# BBTC-PSU.net
KiCad netlist of a schematic drawn in Altium Designer
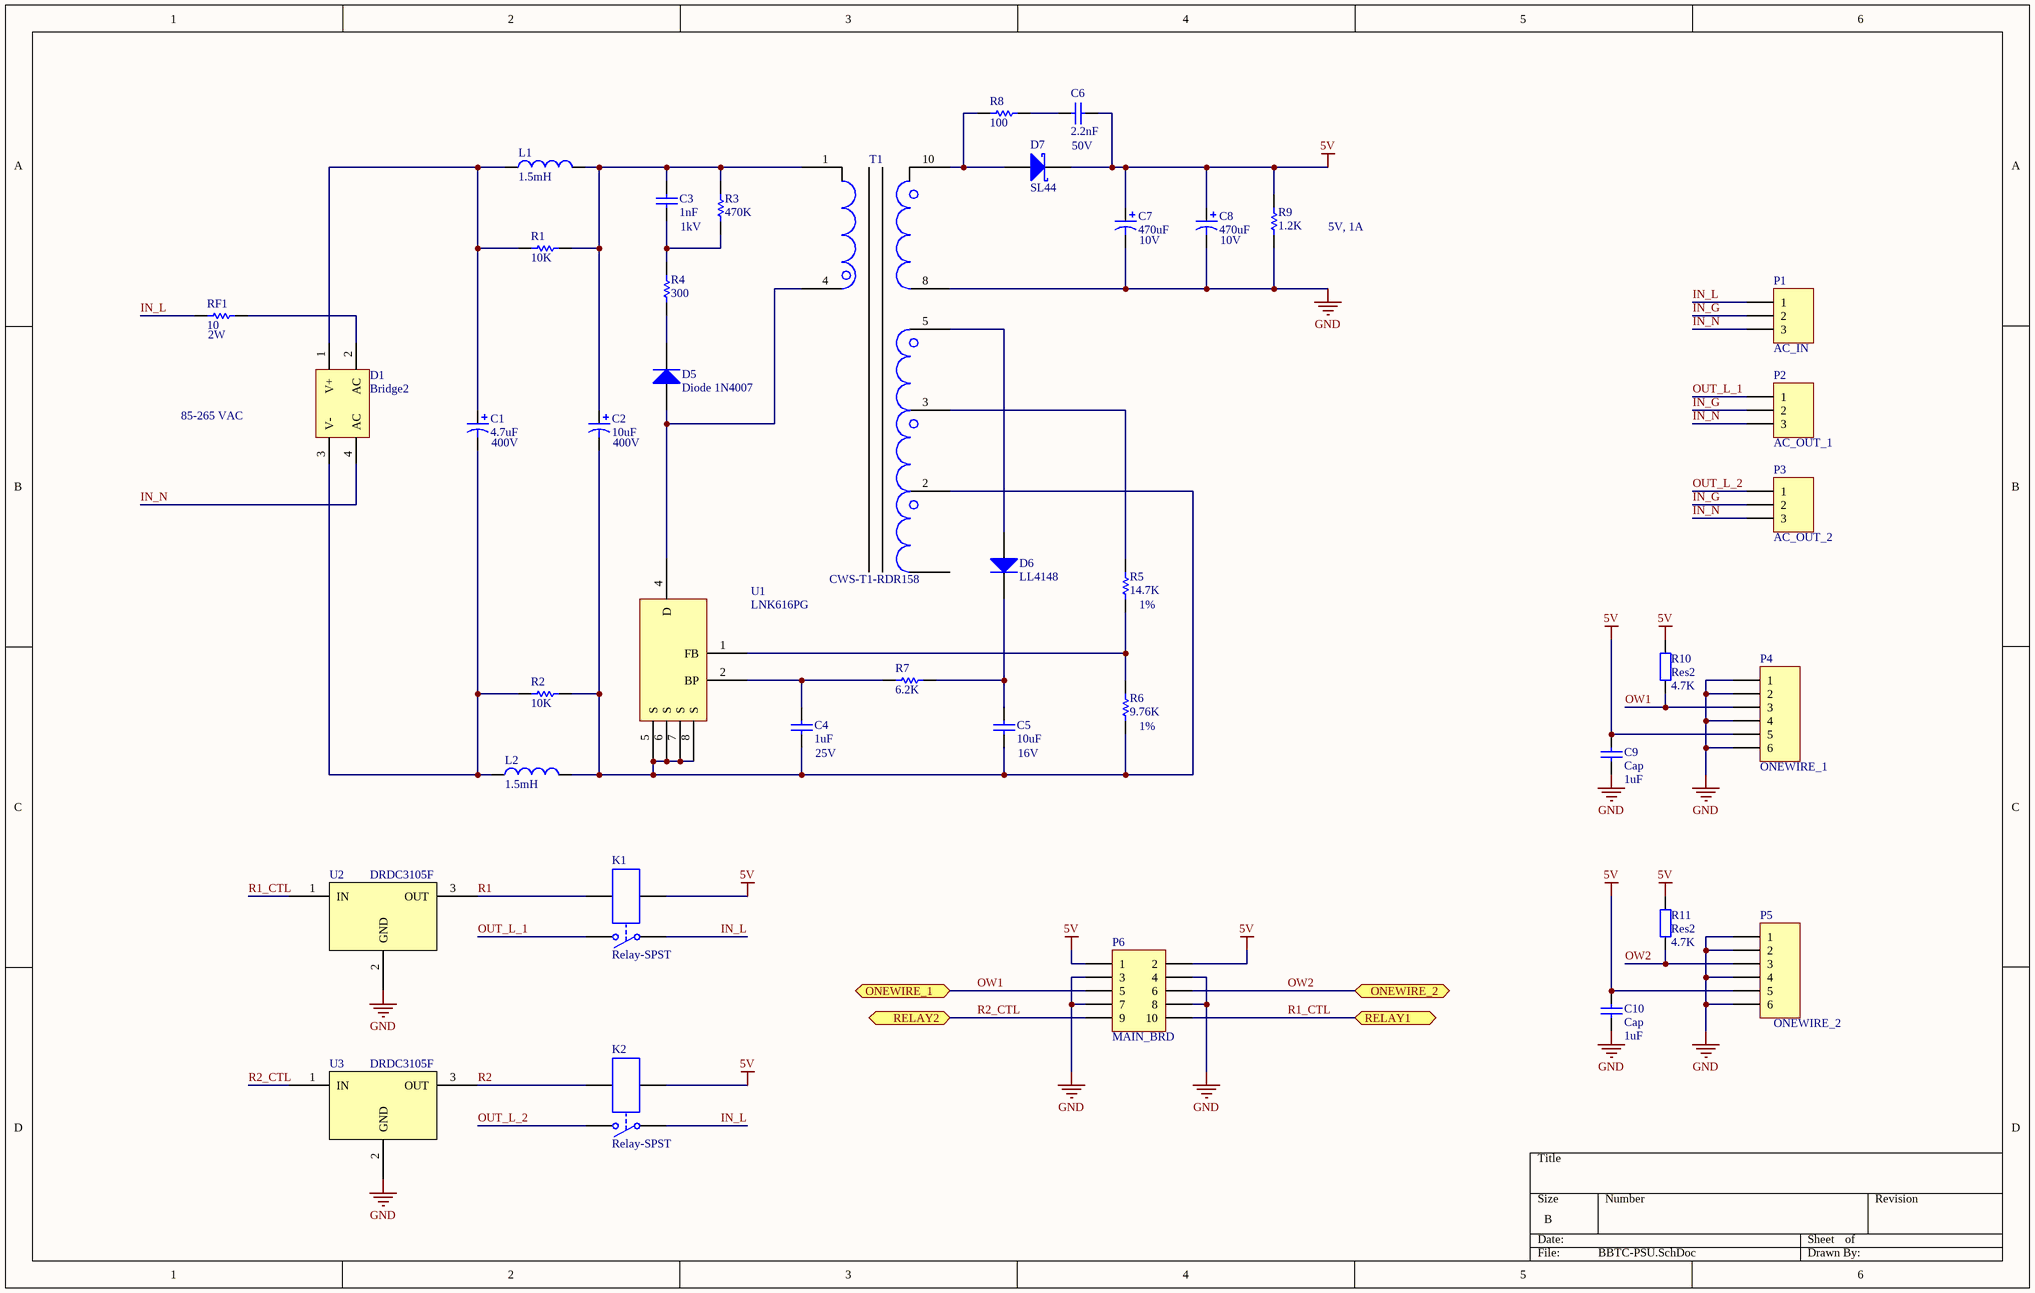
[diagram p0: BBTC-PSU.SchDoc]

(export (version "E")
  (design (tool "Eeschema 10.0.6"))
  (components
    (comp (ref "C1")
      (value "4.7uF")
      (footprint "CAP-10D-5L")
      (description "Polarized Capacitor (Radial)")
      (fields (field (name "VOLTAGE") "400V"))
      (libsource (lib "Miscellaneous Devices") (part "Cap Pol1"))
    )
    (comp (ref "C2")
      (value "10uF")
      (footprint "CAP-12.5D-5L")
      (description "Polarized Capacitor (Radial)")
      (fields (field (name "VOLTAGE") "400V"))
      (libsource (lib "Miscellaneous Devices") (part "Cap Pol1"))
    )
    (comp (ref "C3")
      (value "1nF")
      (footprint "0805")
      (description "Capacitor")
      (fields (field (name "VOLTAGE") "1kV"))
      (libsource (lib "Miscellaneous Devices") (part "Cap"))
    )
    (comp (ref "C4")
      (value "1uF")
      (footprint "0805")
      (description "Capacitor")
      (fields (field (name "VOLTAGE") "25V"))
      (libsource (lib "Miscellaneous Devices") (part "Cap"))
    )
    (comp (ref "C5")
      (value "10uF")
      (footprint "0805")
      (description "Capacitor")
      (fields (field (name "VOLTAGE") "16V"))
      (libsource (lib "Miscellaneous Devices") (part "Cap"))
    )
    (comp (ref "C6")
      (value "2.2nF")
      (footprint "0805")
      (description "Capacitor")
      (fields (field (name "VOLTAGE") "50V"))
      (libsource (lib "Miscellaneous Devices") (part "Cap"))
    )
    (comp (ref "C7")
      (value "470uF")
      (footprint "CAP-8D-3.5L")
      (description "Polarized Capacitor (Radial)")
      (fields (field (name "VOLTAGE") "10V"))
      (libsource (lib "Miscellaneous Devices") (part "Cap Pol1"))
    )
    (comp (ref "C8")
      (value "470uF")
      (footprint "CAP-8D-3.5L")
      (description "Polarized Capacitor (Radial)")
      (fields (field (name "VOLTAGE") "10V"))
      (libsource (lib "Miscellaneous Devices") (part "Cap Pol1"))
    )
    (comp (ref "C9")
      (value "Cap")
      (footprint "0603")
      (description "Capacitor")
      (fields (field (name "ALTIUM_VALUE") "1uF"))
      (libsource (lib "Miscellaneous Devices") (part "Cap"))
    )
    (comp (ref "C10")
      (value "Cap")
      (footprint "0603")
      (description "Capacitor")
      (fields (field (name "ALTIUM_VALUE") "1uF"))
      (libsource (lib "Miscellaneous Devices") (part "Cap"))
    )
    (comp (ref "D1")
      (value "Bridge2")
      (footprint "DF1510S-E3/77")
      (description "Diode Bridge")
      (libsource (lib "Miscellaneous Devices") (part "Bridge2"))
    )
    (comp (ref "D5")
      (value "Diode 1N4007")
      (footprint "Diode-Wide")
      (description "1 Amp General Purpose Rectifier")
      (libsource (lib "Miscellaneous Devices") (part "Diode 1N4007"))
    )
    (comp (ref "D6")
      (value "LL4148")
      (footprint "SOD-80")
      (description "Default Diode")
      (libsource (lib "Miscellaneous Devices") (part "Diode"))
    )
    (comp (ref "D7")
      (value "SL44")
      (footprint "DIODE_SMC")
      (description "Schottky Diode")
      (libsource (lib "Miscellaneous Devices") (part "D Schottky"))
    )
    (comp (ref "K1")
      (value "Relay-SPST")
      (footprint "PB134005")
      (description "Single-Pole Single-Throw Relay")
      (fields (field (name "PUBLISHER") "Altium Limited"))
      (libsource (lib "Miscellaneous Devices") (part "Relay-SPST"))
    )
    (comp (ref "K2")
      (value "Relay-SPST")
      (footprint "PB134005")
      (description "Single-Pole Single-Throw Relay")
      (fields (field (name "PUBLISHER") "Altium Limited"))
      (libsource (lib "Miscellaneous Devices") (part "Relay-SPST"))
    )
    (comp (ref "L1")
      (value "1.5mH")
      (footprint "TSL0808")
      (description "Inductor")
      (libsource (lib "Miscellaneous Devices") (part "Inductor"))
    )
    (comp (ref "L2")
      (value "1.5mH")
      (footprint "TSL0808")
      (description "Inductor")
      (libsource (lib "Miscellaneous Devices") (part "Inductor"))
    )
    (comp (ref "P1")
      (value "AC_IN")
      (footprint "B3P-VH(LF)(SN)")
      (description "Header, 3-Pin")
      (fields (field (name "PUBLISHER") "Altium Limited"))
      (libsource (lib "Miscellaneous Connectors") (part "Header 3"))
    )
    (comp (ref "P2")
      (value "AC_OUT_1")
      (footprint "B3P-VH(LF)(SN)")
      (description "Header, 3-Pin")
      (fields (field (name "PUBLISHER") "Altium Limited"))
      (libsource (lib "Miscellaneous Connectors") (part "Header 3"))
    )
    (comp (ref "P3")
      (value "AC_OUT_2")
      (footprint "B3P-VH(LF)(SN)")
      (description "Header, 3-Pin")
      (fields (field (name "PUBLISHER") "Altium Limited"))
      (libsource (lib "Miscellaneous Connectors") (part "Header 3"))
    )
    (comp (ref "P4")
      (value "ONEWIRE_1")
      (footprint "CONN MOD JACK R/A 6P6C")
      (description "Header, 6-Pin")
      (libsource (lib "Miscellaneous Connectors") (part "Header 6"))
    )
    (comp (ref "P5")
      (value "ONEWIRE_2")
      (footprint "CONN MOD JACK R/A 6P6C")
      (description "Header, 6-Pin")
      (libsource (lib "Miscellaneous Connectors") (part "Header 6"))
    )
    (comp (ref "P6")
      (value "MAIN_BRD")
      (footprint "5X2 PIN PTH HEADER - 2MM")
      (description "Header, 5-Pin, Dual row")
      (libsource (lib "Miscellaneous Connectors") (part "Header 5X2"))
    )
    (comp (ref "R1")
      (value "10K")
      (footprint "1206")
      (description "Resistor")
      (libsource (lib "Miscellaneous Devices") (part "Res1"))
    )
    (comp (ref "R2")
      (value "10K")
      (footprint "1206")
      (description "Resistor")
      (libsource (lib "Miscellaneous Devices") (part "Res1"))
    )
    (comp (ref "R3")
      (value "470K")
      (footprint "0805")
      (description "Resistor")
      (libsource (lib "Miscellaneous Devices") (part "Res1"))
    )
    (comp (ref "R4")
      (value "300")
      (footprint "1206")
      (description "Resistor")
      (libsource (lib "Miscellaneous Devices") (part "Res1"))
    )
    (comp (ref "R5")
      (value "14.7K")
      (footprint "0603")
      (description "Resistor")
      (fields (field (name "TOLERANCE") "1%"))
      (libsource (lib "Miscellaneous Devices") (part "Res1"))
    )
    (comp (ref "R6")
      (value "9.76K")
      (footprint "0603")
      (description "Resistor")
      (fields (field (name "TOLERANCE") "1%"))
      (libsource (lib "Miscellaneous Devices") (part "Res1"))
    )
    (comp (ref "R7")
      (value "6.2K")
      (footprint "0603")
      (description "Resistor")
      (libsource (lib "Miscellaneous Devices") (part "Res1"))
    )
    (comp (ref "R8")
      (value "100")
      (footprint "0805")
      (description "Resistor")
      (libsource (lib "Miscellaneous Devices") (part "Res1"))
    )
    (comp (ref "R9")
      (value "1.2K")
      (footprint "0805")
      (description "Resistor")
      (libsource (lib "Miscellaneous Devices") (part "Res1"))
    )
    (comp (ref "R10")
      (value "Res2")
      (footprint "0603")
      (description "Resistor")
      (fields (field (name "ALTIUM_VALUE") "4.7K"))
      (libsource (lib "Miscellaneous Devices") (part "Res2"))
    )
    (comp (ref "R11")
      (value "Res2")
      (footprint "0603")
      (description "Resistor")
      (fields (field (name "ALTIUM_VALUE") "4.7K"))
      (libsource (lib "Miscellaneous Devices") (part "Res2"))
    )
    (comp (ref "RF1")
      (value "10")
      (footprint "Res Wide")
      (description "Resistor")
      (fields (field (name "POWER") "2W"))
      (libsource (lib "Miscellaneous Devices") (part "Res1"))
    )
    (comp (ref "T1")
      (value "CWS-T1-RDR158")
      (footprint "CWS-T1-RDR158")
      (description "Flyback transformer")
      (libsource (lib "BrewBit") (part "CWS-T1-RDR158"))
    )
    (comp (ref "U1")
      (value "LNK616PG")
      (footprint "LNK6XX")
      (description "Energy-Efficient, Accurate CV/CC Switcher  for Adapters and Chargers")
      (libsource (lib "BrewBit") (part "LNK616PG"))
    )
    (comp (ref "U2")
      (value "DRDC3105F")
      (footprint "SOT23")
      (description "INTEGRATED RELAY, INDUCTIVE LOAD DRIVER")
      (libsource (lib "BrewBit") (part "DRDC3105F"))
    )
    (comp (ref "U3")
      (value "DRDC3105F")
      (footprint "SOT23")
      (description "INTEGRATED RELAY, INDUCTIVE LOAD DRIVER")
      (libsource (lib "BrewBit") (part "DRDC3105F"))
    )
  )
  (nets
    (net (code "1") (name "/IN_G") (class "Default")
      (node (ref "P1") (pin "2") (pinfunction "2_2") (pintype "passive"))
      (node (ref "P2") (pin "2") (pinfunction "2_2") (pintype "passive"))
      (node (ref "P3") (pin "2") (pinfunction "2_2") (pintype "passive"))
    )
    (net (code "2") (name "/IN_L") (class "Default")
      (node (ref "K1") (pin "1") (pinfunction "1_1") (pintype "passive"))
      (node (ref "K2") (pin "1") (pinfunction "1_1") (pintype "passive"))
      (node (ref "P1") (pin "1") (pinfunction "1_1") (pintype "passive"))
      (node (ref "RF1") (pin "1") (pinfunction "1_1") (pintype "passive"))
    )
    (net (code "3") (name "/IN_N") (class "Default")
      (node (ref "D1") (pin "4") (pinfunction "AC_4") (pintype "passive"))
      (node (ref "P1") (pin "3") (pinfunction "3_3") (pintype "passive"))
      (node (ref "P2") (pin "3") (pinfunction "3_3") (pintype "passive"))
      (node (ref "P3") (pin "3") (pinfunction "3_3") (pintype "passive"))
    )
    (net (code "4") (name "/OUT_L_1") (class "Default")
      (node (ref "K1") (pin "2") (pinfunction "2_2") (pintype "passive"))
      (node (ref "P2") (pin "1") (pinfunction "1_1") (pintype "passive"))
    )
    (net (code "5") (name "/OUT_L_2") (class "Default")
      (node (ref "K2") (pin "2") (pinfunction "2_2") (pintype "passive"))
      (node (ref "P3") (pin "1") (pinfunction "1_1") (pintype "passive"))
    )
    (net (code "6") (name "/OW1") (class "Default")
      (node (ref "P4") (pin "3") (pinfunction "3_3") (pintype "passive"))
      (node (ref "P6") (pin "5") (pinfunction "5_5") (pintype "passive"))
      (node (ref "R10") (pin "1") (pinfunction "1_1") (pintype "passive"))
    )
    (net (code "7") (name "/OW2") (class "Default")
      (node (ref "P5") (pin "3") (pinfunction "3_3") (pintype "passive"))
      (node (ref "P6") (pin "6") (pinfunction "6_6") (pintype "passive"))
      (node (ref "R11") (pin "1") (pinfunction "1_1") (pintype "passive"))
    )
    (net (code "8") (name "/R1") (class "Default")
      (node (ref "K1") (pin "4") (pinfunction "4_4") (pintype "passive"))
      (node (ref "U2") (pin "3") (pinfunction "OUT_3") (pintype "passive"))
    )
    (net (code "9") (name "/R1_CTL") (class "Default")
      (node (ref "P6") (pin "10") (pinfunction "10_10") (pintype "passive"))
      (node (ref "U2") (pin "1") (pinfunction "IN_1") (pintype "passive"))
    )
    (net (code "10") (name "/R2") (class "Default")
      (node (ref "K2") (pin "4") (pinfunction "4_4") (pintype "passive"))
      (node (ref "U3") (pin "3") (pinfunction "OUT_3") (pintype "passive"))
    )
    (net (code "11") (name "/R2_CTL") (class "Default")
      (node (ref "P6") (pin "9") (pinfunction "9_9") (pintype "passive"))
      (node (ref "U3") (pin "1") (pinfunction "IN_1") (pintype "passive"))
    )
    (net (code "12") (name "5V") (class "Default")
      (node (ref "C10") (pin "2") (pinfunction "2_2") (pintype "passive"))
      (node (ref "C6") (pin "1") (pinfunction "1_1") (pintype "passive"))
      (node (ref "C7") (pin "1") (pinfunction "1_1") (pintype "passive"))
      (node (ref "C8") (pin "1") (pinfunction "1_1") (pintype "passive"))
      (node (ref "C9") (pin "2") (pinfunction "2_2") (pintype "passive"))
      (node (ref "D7") (pin "2") (pinfunction "K_2") (pintype "passive"))
      (node (ref "K1") (pin "3") (pinfunction "3_3") (pintype "passive"))
      (node (ref "K2") (pin "3") (pinfunction "3_3") (pintype "passive"))
      (node (ref "P4") (pin "5") (pinfunction "5_5") (pintype "passive"))
      (node (ref "P5") (pin "5") (pinfunction "5_5") (pintype "passive"))
      (node (ref "P6") (pin "1") (pinfunction "1_1") (pintype "passive"))
      (node (ref "P6") (pin "2") (pinfunction "2_2") (pintype "passive"))
      (node (ref "R10") (pin "2") (pinfunction "2_2") (pintype "passive"))
      (node (ref "R11") (pin "2") (pinfunction "2_2") (pintype "passive"))
      (node (ref "R9") (pin "1") (pinfunction "1_1") (pintype "passive"))
    )
    (net (code "13") (name "GND") (class "Default")
      (node (ref "C10") (pin "1") (pinfunction "1_1") (pintype "passive"))
      (node (ref "C7") (pin "2") (pinfunction "2_2") (pintype "passive"))
      (node (ref "C8") (pin "2") (pinfunction "2_2") (pintype "passive"))
      (node (ref "C9") (pin "1") (pinfunction "1_1") (pintype "passive"))
      (node (ref "P4") (pin "1") (pinfunction "1_1") (pintype "passive"))
      (node (ref "P4") (pin "2") (pinfunction "2_2") (pintype "passive"))
      (node (ref "P4") (pin "4") (pinfunction "4_4") (pintype "passive"))
      (node (ref "P4") (pin "6") (pinfunction "6_6") (pintype "passive"))
      (node (ref "P5") (pin "1") (pinfunction "1_1") (pintype "passive"))
      (node (ref "P5") (pin "2") (pinfunction "2_2") (pintype "passive"))
      (node (ref "P5") (pin "4") (pinfunction "4_4") (pintype "passive"))
      (node (ref "P5") (pin "6") (pinfunction "6_6") (pintype "passive"))
      (node (ref "P6") (pin "3") (pinfunction "3_3") (pintype "passive"))
      (node (ref "P6") (pin "4") (pinfunction "4_4") (pintype "passive"))
      (node (ref "P6") (pin "7") (pinfunction "7_7") (pintype "passive"))
      (node (ref "P6") (pin "8") (pinfunction "8_8") (pintype "passive"))
      (node (ref "R9") (pin "2") (pinfunction "2_2") (pintype "passive"))
      (node (ref "T1") (pin "8") (pintype "passive"))
      (node (ref "U2") (pin "2") (pinfunction "GND_2") (pintype "passive"))
      (node (ref "U3") (pin "2") (pinfunction "GND_2") (pintype "passive"))
    )
    (net (code "14") (name "Net-(C2-Pad1)") (class "Default")
      (node (ref "C2") (pin "1") (pinfunction "1_1") (pintype "passive"))
      (node (ref "C3") (pin "1") (pinfunction "1_1") (pintype "passive"))
      (node (ref "L1") (pin "2") (pinfunction "2_2") (pintype "passive"))
      (node (ref "R1") (pin "2") (pinfunction "2_2") (pintype "passive"))
      (node (ref "R3") (pin "2") (pinfunction "2_2") (pintype "passive"))
      (node (ref "T1") (pin "1") (pintype "passive"))
    )
    (net (code "15") (name "Net-(C2-Pad2)") (class "Default")
      (node (ref "C2") (pin "2") (pinfunction "2_2") (pintype "passive"))
      (node (ref "C4") (pin "2") (pinfunction "2_2") (pintype "passive"))
      (node (ref "C5") (pin "2") (pinfunction "2_2") (pintype "passive"))
      (node (ref "L2") (pin "2") (pinfunction "2_2") (pintype "passive"))
      (node (ref "R2") (pin "2") (pinfunction "2_2") (pintype "passive"))
      (node (ref "R6") (pin "2") (pinfunction "2_2") (pintype "passive"))
      (node (ref "T1") (pin "2") (pintype "passive"))
      (node (ref "U1") (pin "5") (pinfunction "S_5") (pintype "passive"))
      (node (ref "U1") (pin "6") (pinfunction "S_6") (pintype "passive"))
      (node (ref "U1") (pin "7") (pinfunction "S_7") (pintype "passive"))
      (node (ref "U1") (pin "8") (pinfunction "S_8") (pintype "passive"))
    )
    (net (code "16") (name "Net-(C3-Pad2)") (class "Default")
      (node (ref "C3") (pin "2") (pinfunction "2_2") (pintype "passive"))
      (node (ref "R3") (pin "1") (pinfunction "1_1") (pintype "passive"))
      (node (ref "R4") (pin "2") (pinfunction "2_2") (pintype "passive"))
    )
    (net (code "17") (name "Net-(C6-Pad2)") (class "Default")
      (node (ref "C6") (pin "2") (pinfunction "2_2") (pintype "passive"))
      (node (ref "R8") (pin "1") (pinfunction "1_1") (pintype "passive"))
    )
    (net (code "18") (name "Net-(D1-AC-Pad2)") (class "Default")
      (node (ref "D1") (pin "2") (pinfunction "AC_2") (pintype "passive"))
      (node (ref "RF1") (pin "2") (pinfunction "2_2") (pintype "passive"))
    )
    (net (code "19") (name "Net-(D1-V+)") (class "Default")
      (node (ref "C1") (pin "1") (pinfunction "1_1") (pintype "passive"))
      (node (ref "D1") (pin "1") (pinfunction "V+_1") (pintype "passive"))
      (node (ref "L1") (pin "1") (pinfunction "1_1") (pintype "passive"))
      (node (ref "R1") (pin "1") (pinfunction "1_1") (pintype "passive"))
    )
    (net (code "20") (name "Net-(D1-V-)") (class "Default")
      (node (ref "C1") (pin "2") (pinfunction "2_2") (pintype "passive"))
      (node (ref "D1") (pin "3") (pinfunction "V-_3") (pintype "passive"))
      (node (ref "L2") (pin "1") (pinfunction "1_1") (pintype "passive"))
      (node (ref "R2") (pin "1") (pinfunction "1_1") (pintype "passive"))
    )
    (net (code "21") (name "Net-(D5-A)") (class "Default")
      (node (ref "D5") (pin "1") (pinfunction "A_1") (pintype "passive"))
      (node (ref "T1") (pin "4") (pintype "passive"))
      (node (ref "U1") (pin "4") (pinfunction "D_4") (pintype "passive"))
    )
    (net (code "22") (name "Net-(D5-K)") (class "Default")
      (node (ref "D5") (pin "2") (pinfunction "K_2") (pintype "passive"))
      (node (ref "R4") (pin "1") (pinfunction "1_1") (pintype "passive"))
    )
    (net (code "23") (name "Net-(D6-A)") (class "Default")
      (node (ref "D6") (pin "1") (pinfunction "A_1") (pintype "passive"))
      (node (ref "T1") (pin "5") (pintype "passive"))
    )
    (net (code "24") (name "Net-(D6-K)") (class "Default")
      (node (ref "C5") (pin "1") (pinfunction "1_1") (pintype "passive"))
      (node (ref "D6") (pin "2") (pinfunction "K_2") (pintype "passive"))
      (node (ref "R7") (pin "1") (pinfunction "1_1") (pintype "passive"))
    )
    (net (code "25") (name "Net-(D7-A)") (class "Default")
      (node (ref "D7") (pin "1") (pinfunction "A_1") (pintype "passive"))
      (node (ref "R8") (pin "2") (pinfunction "2_2") (pintype "passive"))
      (node (ref "T1") (pin "10") (pintype "passive"))
    )
    (net (code "26") (name "Net-(R5-Pad1)") (class "Default")
      (node (ref "R5") (pin "1") (pinfunction "1_1") (pintype "passive"))
      (node (ref "T1") (pin "3") (pintype "passive"))
    )
    (net (code "27") (name "Net-(U1-BP)") (class "Default")
      (node (ref "C4") (pin "1") (pinfunction "1_1") (pintype "passive"))
      (node (ref "R7") (pin "2") (pinfunction "2_2") (pintype "passive"))
      (node (ref "U1") (pin "2") (pinfunction "BP_2") (pintype "passive"))
    )
    (net (code "28") (name "Net-(U1-FB)") (class "Default")
      (node (ref "R5") (pin "2") (pinfunction "2_2") (pintype "passive"))
      (node (ref "R6") (pin "1") (pinfunction "1_1") (pintype "passive"))
      (node (ref "U1") (pin "1") (pinfunction "FB_1") (pintype "passive"))
    )
  )
)
